# protocol-bridge.net
KiCad netlist of a schematic drawn in Altium Designer
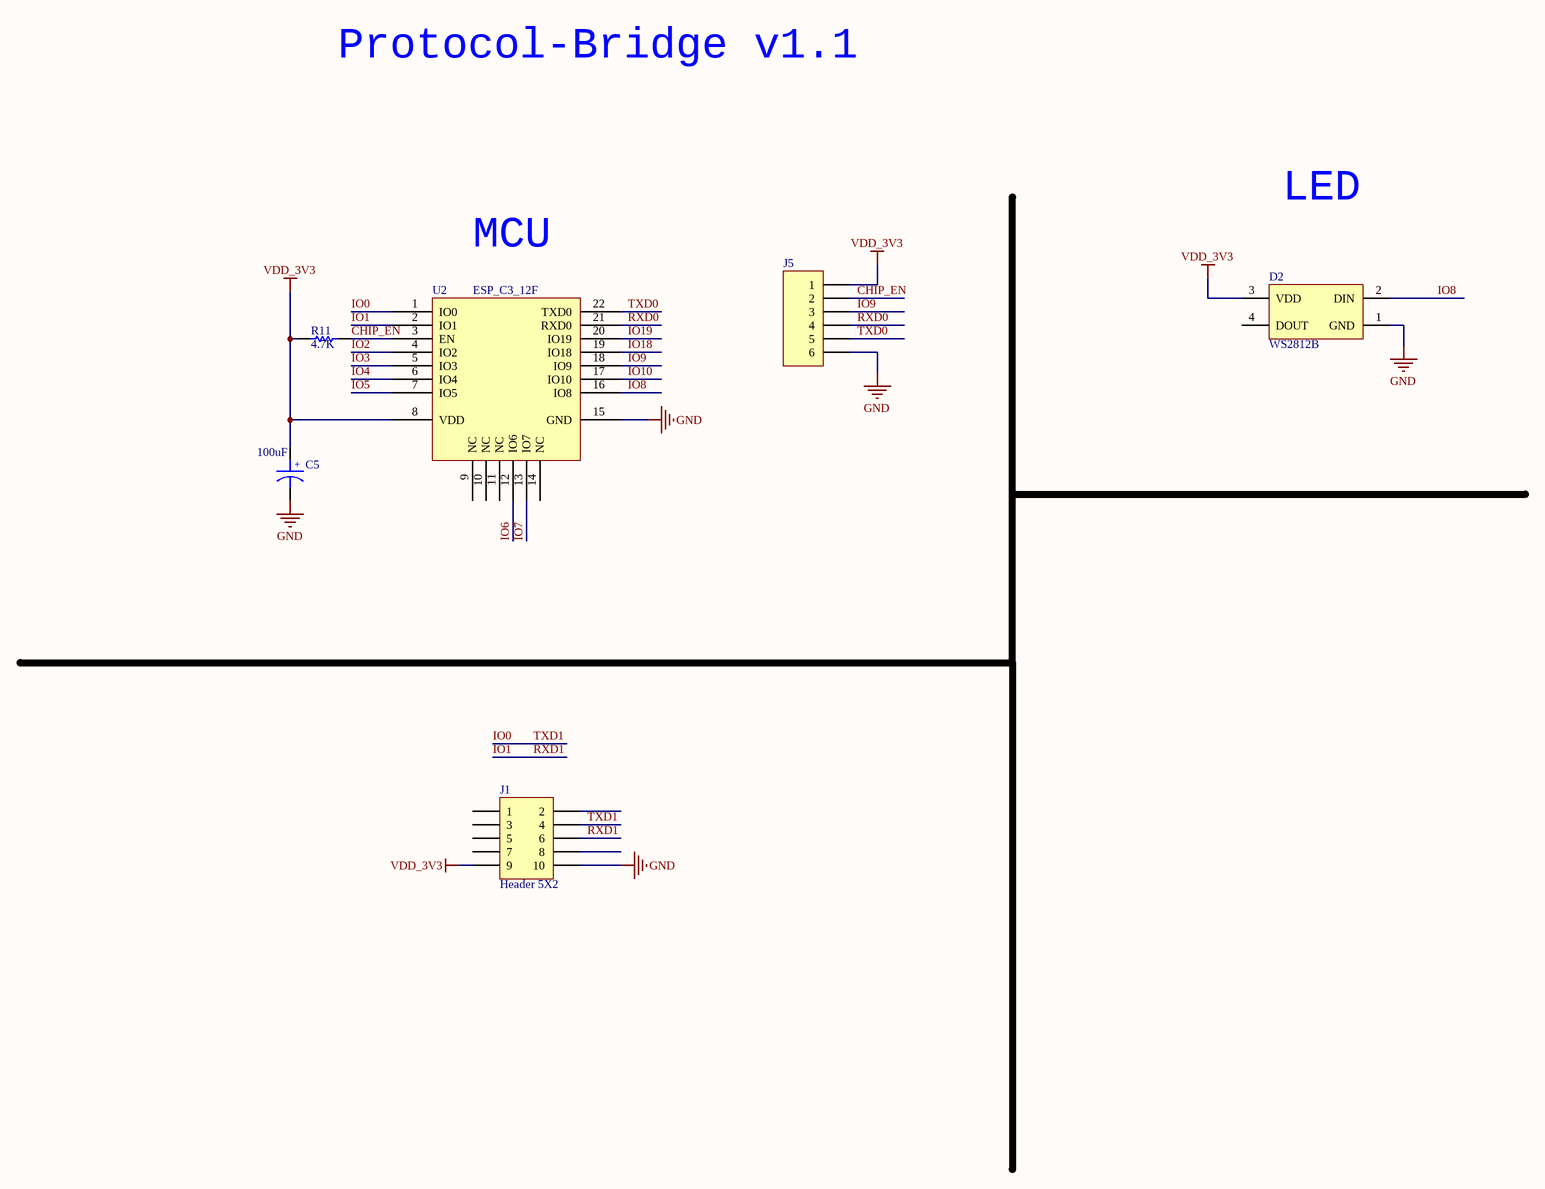
[diagram p0: protocol-bridge.SchDoc]

(export (version "E")
  (design (tool "Eeschema 10.0.6"))
  (components
    (comp (ref "C5")
      (value "100uF")
      (footprint "SMT_C_Tantalum_B")
      (description "Capacitor, SM Tantalum; Body 3.5 x 2.8 mm (LxW typ)")
      (libsource (lib "Vowstar_Basic_Device") (part "SMT_C_Tantalum_B"))
    )
    (comp (ref "D2")
      (value "WS2812B")
      (footprint "LED 3528-4Pin")
      (libsource (lib "nanoESP32S2") (part "WS2812B"))
    )
    (comp (ref "J1")
      (value "Header 5X2")
      (footprint "HEAD_1.27_5x2")
      (description "Header, 5-Pin, Dual row")
      (fields (field (name "MANUFACTURER") "Generic Components"))
      (libsource (lib "nanoDAP") (part "Header 5X2"))
    )
    (comp (ref "J5")
      (value "~")
      (footprint "HEADER_1.27_SMT_6x1")
      (description "Header, 4-Pin")
      (fields (field (name "PUBLISHER") "Altium Limited"))
      (libsource (lib "sot-target") (part "Header_6"))
    )
    (comp (ref "R11")
      (value "4.7K")
      (footprint "0603_R")
      (description "Resistor")
      (fields (field (name "PUBLISHER") "Altium Limited"))
      (libsource (lib "MYLIB") (part "0603-1"))
    )
    (comp (ref "U2")
      (value "ESP_C3_12F")
      (footprint "ESP-C3-12F")
      (description "ESP-12 Wi-Fi Module by AI-Thinker")
      (libsource (lib "sot-target") (part "ESP32_C3_12F"))
    )
  )
  (nets
    (net (code "1") (name "/CHIP_EN") (class "Default")
      (node (ref "J5") (pin "2") (pinfunction "2_2") (pintype "passive"))
      (node (ref "R11") (pin "1") (pinfunction "1_1") (pintype "passive"))
      (node (ref "U2") (pin "3") (pinfunction "EN_3") (pintype "passive"))
    )
    (net (code "2") (name "/IO0") (class "Default")
      (node (ref "J1") (pin "4") (pinfunction "4_4") (pintype "passive"))
      (node (ref "U2") (pin "1") (pinfunction "IO0_1") (pintype "passive"))
    )
    (net (code "3") (name "/IO1") (class "Default")
      (node (ref "J1") (pin "6") (pinfunction "6_6") (pintype "passive"))
      (node (ref "U2") (pin "2") (pinfunction "IO1_2") (pintype "passive"))
    )
    (net (code "4") (name "/IO2") (class "Default")
      (node (ref "U2") (pin "4") (pinfunction "IO2_4") (pintype "passive"))
    )
    (net (code "5") (name "/IO3") (class "Default")
      (node (ref "U2") (pin "5") (pinfunction "IO3_5") (pintype "passive"))
    )
    (net (code "6") (name "/IO4") (class "Default")
      (node (ref "U2") (pin "6") (pinfunction "IO4_6") (pintype "passive"))
    )
    (net (code "7") (name "/IO5") (class "Default")
      (node (ref "U2") (pin "7") (pinfunction "IO5_7") (pintype "passive"))
    )
    (net (code "8") (name "/IO6") (class "Default")
      (node (ref "U2") (pin "12") (pinfunction "IO6_12") (pintype "passive"))
    )
    (net (code "9") (name "/IO7") (class "Default")
      (node (ref "U2") (pin "13") (pinfunction "IO7_13") (pintype "passive"))
    )
    (net (code "10") (name "/IO8") (class "Default")
      (node (ref "D2") (pin "2") (pinfunction "DIN_2") (pintype "passive"))
      (node (ref "U2") (pin "16") (pinfunction "IO8_16") (pintype "passive"))
    )
    (net (code "11") (name "/IO9") (class "Default")
      (node (ref "J5") (pin "3") (pinfunction "3_3") (pintype "passive"))
      (node (ref "U2") (pin "18") (pinfunction "IO9_18") (pintype "passive"))
    )
    (net (code "12") (name "/IO10") (class "Default")
      (node (ref "U2") (pin "17") (pinfunction "IO10_17") (pintype "passive"))
    )
    (net (code "13") (name "/IO18") (class "Default")
      (node (ref "U2") (pin "19") (pinfunction "IO18_19") (pintype "passive"))
    )
    (net (code "14") (name "/IO19") (class "Default")
      (node (ref "U2") (pin "20") (pinfunction "IO19_20") (pintype "passive"))
    )
    (net (code "15") (name "/RXD0") (class "Default")
      (node (ref "J5") (pin "4") (pinfunction "4_4") (pintype "passive"))
      (node (ref "U2") (pin "21") (pinfunction "RXD0_21") (pintype "passive"))
    )
    (net (code "16") (name "/TXD0") (class "Default")
      (node (ref "J5") (pin "5") (pinfunction "5_5") (pintype "passive"))
      (node (ref "U2") (pin "22") (pinfunction "TXD0_22") (pintype "passive"))
    )
    (net (code "17") (name "GND") (class "Default")
      (node (ref "C5") (pin "2") (pinfunction "2_2") (pintype "passive"))
      (node (ref "D2") (pin "1") (pinfunction "GND_1") (pintype "passive"))
      (node (ref "J1") (pin "10") (pinfunction "10_10") (pintype "passive"))
      (node (ref "J5") (pin "6") (pinfunction "6_6") (pintype "passive"))
      (node (ref "U2") (pin "15") (pinfunction "GND_15") (pintype "passive"))
    )
    (net (code "18") (name "VDD_3V3") (class "Default")
      (node (ref "C5") (pin "1") (pinfunction "1_1") (pintype "passive"))
      (node (ref "D2") (pin "3") (pinfunction "VDD_3") (pintype "passive"))
      (node (ref "J1") (pin "9") (pinfunction "9_9") (pintype "passive"))
      (node (ref "J5") (pin "1") (pinfunction "1_1") (pintype "passive"))
      (node (ref "R11") (pin "2") (pinfunction "2_2") (pintype "passive"))
      (node (ref "U2") (pin "8") (pinfunction "VDD_8") (pintype "passive"))
    )
    (net (code "19") (name "unconnected-(D2-DOUT-Pad4)") (class "Default")
      (node (ref "D2") (pin "4") (pinfunction "DOUT_4") (pintype "passive"))
    )
    (net (code "20") (name "unconnected-(J1-Pad1)") (class "Default")
      (node (ref "J1") (pin "1") (pinfunction "1_1") (pintype "passive"))
    )
    (net (code "21") (name "unconnected-(J1-Pad2)") (class "Default")
      (node (ref "J1") (pin "2") (pinfunction "2_2") (pintype "passive"))
    )
    (net (code "22") (name "unconnected-(J1-Pad3)") (class "Default")
      (node (ref "J1") (pin "3") (pinfunction "3_3") (pintype "passive"))
    )
    (net (code "23") (name "unconnected-(J1-Pad5)") (class "Default")
      (node (ref "J1") (pin "5") (pinfunction "5_5") (pintype "passive"))
    )
    (net (code "24") (name "unconnected-(J1-Pad7)") (class "Default")
      (node (ref "J1") (pin "7") (pinfunction "7_7") (pintype "passive"))
    )
    (net (code "25") (name "unconnected-(J1-Pad8)") (class "Default")
      (node (ref "J1") (pin "8") (pinfunction "8_8") (pintype "passive"))
    )
    (net (code "26") (name "unconnected-(U2-NC-Pad9)") (class "Default")
      (node (ref "U2") (pin "9") (pinfunction "NC_9") (pintype "passive"))
    )
    (net (code "27") (name "unconnected-(U2-NC-Pad10)") (class "Default")
      (node (ref "U2") (pin "10") (pinfunction "NC_10") (pintype "passive"))
    )
    (net (code "28") (name "unconnected-(U2-NC-Pad11)") (class "Default")
      (node (ref "U2") (pin "11") (pinfunction "NC_11") (pintype "passive"))
    )
    (net (code "29") (name "unconnected-(U2-NC-Pad14)") (class "Default")
      (node (ref "U2") (pin "14") (pinfunction "NC_14") (pintype "passive"))
    )
  )
)
